# LED.net
KiCad netlist of a schematic drawn in Altium Designer
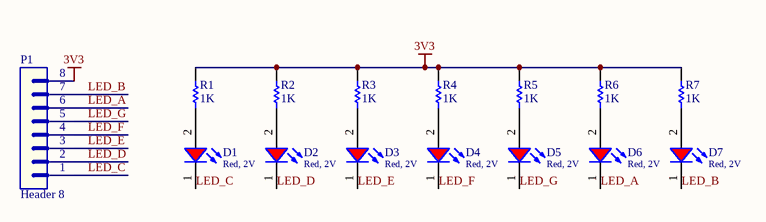
[diagram p0: LED.SchDoc]

(export (version "E")
  (design (tool "Eeschema 10.0.6"))
  (components
    (comp (ref "D1")
      (value "Red, 2V")
      (footprint "WL-SMCW_0805")
      (description "WL-SMCW SMT Mono-color Chip LED Waterclear, size 0805, Red, 2V, 140deg")
      (fields (field (name "PART NUMBER") "150080RS75000") (field (name "PUBLISHER") "Wurth Elektronik"))
      (libsource (lib "LED_GREEN") (part "150080RS75000"))
    )
    (comp (ref "D2")
      (value "Red, 2V")
      (footprint "WL-SMCW_0805")
      (description "WL-SMCW SMT Mono-color Chip LED Waterclear, size 0805, Red, 2V, 140deg")
      (fields (field (name "PART NUMBER") "150080RS75000") (field (name "PUBLISHER") "Wurth Elektronik"))
      (libsource (lib "LED_GREEN") (part "150080RS75000"))
    )
    (comp (ref "D3")
      (value "Red, 2V")
      (footprint "WL-SMCW_0805")
      (description "WL-SMCW SMT Mono-color Chip LED Waterclear, size 0805, Red, 2V, 140deg")
      (fields (field (name "PART NUMBER") "150080RS75000") (field (name "PUBLISHER") "Wurth Elektronik"))
      (libsource (lib "LED_GREEN") (part "150080RS75000"))
    )
    (comp (ref "D4")
      (value "Red, 2V")
      (footprint "WL-SMCW_0805")
      (description "WL-SMCW SMT Mono-color Chip LED Waterclear, size 0805, Red, 2V, 140deg")
      (fields (field (name "PART NUMBER") "150080RS75000") (field (name "PUBLISHER") "Wurth Elektronik"))
      (libsource (lib "LED_GREEN") (part "150080RS75000"))
    )
    (comp (ref "D5")
      (value "Red, 2V")
      (footprint "WL-SMCW_0805")
      (description "WL-SMCW SMT Mono-color Chip LED Waterclear, size 0805, Red, 2V, 140deg")
      (fields (field (name "PART NUMBER") "150080RS75000") (field (name "PUBLISHER") "Wurth Elektronik"))
      (libsource (lib "LED_GREEN") (part "150080RS75000"))
    )
    (comp (ref "D6")
      (value "Red, 2V")
      (footprint "WL-SMCW_0805")
      (description "WL-SMCW SMT Mono-color Chip LED Waterclear, size 0805, Red, 2V, 140deg")
      (fields (field (name "PART NUMBER") "150080RS75000") (field (name "PUBLISHER") "Wurth Elektronik"))
      (libsource (lib "LED_GREEN") (part "150080RS75000"))
    )
    (comp (ref "D7")
      (value "Red, 2V")
      (footprint "WL-SMCW_0805")
      (description "WL-SMCW SMT Mono-color Chip LED Waterclear, size 0805, Red, 2V, 140deg")
      (fields (field (name "PART NUMBER") "150080RS75000") (field (name "PUBLISHER") "Wurth Elektronik"))
      (libsource (lib "LED_GREEN") (part "150080RS75000"))
    )
    (comp (ref "P1")
      (value "Header 8")
      (footprint "JP8")
      (description "Header, 8-Pin")
      (fields (field (name "PUBLISHER") "Altium Limited"))
      (libsource (lib "Header-connector") (part "Header 8"))
    )
    (comp (ref "R1")
      (value "1K")
      (footprint "Resistor:RES-SM-0805")
      (description "RES 1K OHM 1% 1/4W 0805")
      (fields
        (field (name "MANUFACTURER") "Stackpole Electronics Inc")
        (field (name "MANUFACTURER PART NUMBER") "RNCP0805FTD1K00")
      )
      (libsource (lib "Resistor") (part "Res-1K-0805"))
    )
    (comp (ref "R2")
      (value "1K")
      (footprint "Resistor:RES-SM-0805")
      (description "RES 1K OHM 1% 1/4W 0805")
      (fields
        (field (name "MANUFACTURER") "Stackpole Electronics Inc")
        (field (name "MANUFACTURER PART NUMBER") "RNCP0805FTD1K00")
      )
      (libsource (lib "Resistor") (part "Res-1K-0805"))
    )
    (comp (ref "R3")
      (value "1K")
      (footprint "Resistor:RES-SM-0805")
      (description "RES 1K OHM 1% 1/4W 0805")
      (fields
        (field (name "MANUFACTURER") "Stackpole Electronics Inc")
        (field (name "MANUFACTURER PART NUMBER") "RNCP0805FTD1K00")
      )
      (libsource (lib "Resistor") (part "Res-1K-0805"))
    )
    (comp (ref "R4")
      (value "1K")
      (footprint "Resistor:RES-SM-0805")
      (description "RES 1K OHM 1% 1/4W 0805")
      (fields
        (field (name "MANUFACTURER") "Stackpole Electronics Inc")
        (field (name "MANUFACTURER PART NUMBER") "RNCP0805FTD1K00")
      )
      (libsource (lib "Resistor") (part "Res-1K-0805"))
    )
    (comp (ref "R5")
      (value "1K")
      (footprint "Resistor:RES-SM-0805")
      (description "RES 1K OHM 1% 1/4W 0805")
      (fields
        (field (name "MANUFACTURER") "Stackpole Electronics Inc")
        (field (name "MANUFACTURER PART NUMBER") "RNCP0805FTD1K00")
      )
      (libsource (lib "Resistor") (part "Res-1K-0805"))
    )
    (comp (ref "R6")
      (value "1K")
      (footprint "Resistor:RES-SM-0805")
      (description "RES 1K OHM 1% 1/4W 0805")
      (fields
        (field (name "MANUFACTURER") "Stackpole Electronics Inc")
        (field (name "MANUFACTURER PART NUMBER") "RNCP0805FTD1K00")
      )
      (libsource (lib "Resistor") (part "Res-1K-0805"))
    )
    (comp (ref "R7")
      (value "1K")
      (footprint "Resistor:RES-SM-0805")
      (description "RES 1K OHM 1% 1/4W 0805")
      (fields
        (field (name "MANUFACTURER") "Stackpole Electronics Inc")
        (field (name "MANUFACTURER PART NUMBER") "RNCP0805FTD1K00")
      )
      (libsource (lib "Resistor") (part "Res-1K-0805"))
    )
  )
  (nets
    (net (code "1") (name "/LED_A") (class "Default")
      (node (ref "D6") (pin "1") (pinfunction "K_1") (pintype "passive"))
      (node (ref "P1") (pin "6") (pinfunction "6_6") (pintype "passive"))
    )
    (net (code "2") (name "/LED_B") (class "Default")
      (node (ref "D7") (pin "1") (pinfunction "K_1") (pintype "passive"))
      (node (ref "P1") (pin "7") (pinfunction "7_7") (pintype "passive"))
    )
    (net (code "3") (name "/LED_C") (class "Default")
      (node (ref "D1") (pin "1") (pinfunction "K_1") (pintype "passive"))
      (node (ref "P1") (pin "1") (pinfunction "1_1") (pintype "passive"))
    )
    (net (code "4") (name "/LED_D") (class "Default")
      (node (ref "D2") (pin "1") (pinfunction "K_1") (pintype "passive"))
      (node (ref "P1") (pin "2") (pinfunction "2_2") (pintype "passive"))
    )
    (net (code "5") (name "/LED_E") (class "Default")
      (node (ref "D3") (pin "1") (pinfunction "K_1") (pintype "passive"))
      (node (ref "P1") (pin "3") (pinfunction "3_3") (pintype "passive"))
    )
    (net (code "6") (name "/LED_F") (class "Default")
      (node (ref "D4") (pin "1") (pinfunction "K_1") (pintype "passive"))
      (node (ref "P1") (pin "4") (pinfunction "4_4") (pintype "passive"))
    )
    (net (code "7") (name "/LED_G") (class "Default")
      (node (ref "D5") (pin "1") (pinfunction "K_1") (pintype "passive"))
      (node (ref "P1") (pin "5") (pinfunction "5_5") (pintype "passive"))
    )
    (net (code "8") (name "3V3") (class "Default")
      (node (ref "P1") (pin "8") (pinfunction "8_8") (pintype "passive"))
      (node (ref "R1") (pin "2") (pinfunction "2_2") (pintype "passive"))
      (node (ref "R2") (pin "2") (pinfunction "2_2") (pintype "passive"))
      (node (ref "R3") (pin "2") (pinfunction "2_2") (pintype "passive"))
      (node (ref "R4") (pin "2") (pinfunction "2_2") (pintype "passive"))
      (node (ref "R5") (pin "2") (pinfunction "2_2") (pintype "passive"))
      (node (ref "R6") (pin "2") (pinfunction "2_2") (pintype "passive"))
      (node (ref "R7") (pin "2") (pinfunction "2_2") (pintype "passive"))
    )
    (net (code "9") (name "Net-(D1-A)") (class "Default")
      (node (ref "D1") (pin "2") (pinfunction "A_2") (pintype "passive"))
      (node (ref "R1") (pin "1") (pinfunction "1_1") (pintype "passive"))
    )
    (net (code "10") (name "Net-(D2-A)") (class "Default")
      (node (ref "D2") (pin "2") (pinfunction "A_2") (pintype "passive"))
      (node (ref "R2") (pin "1") (pinfunction "1_1") (pintype "passive"))
    )
    (net (code "11") (name "Net-(D3-A)") (class "Default")
      (node (ref "D3") (pin "2") (pinfunction "A_2") (pintype "passive"))
      (node (ref "R3") (pin "1") (pinfunction "1_1") (pintype "passive"))
    )
    (net (code "12") (name "Net-(D4-A)") (class "Default")
      (node (ref "D4") (pin "2") (pinfunction "A_2") (pintype "passive"))
      (node (ref "R4") (pin "1") (pinfunction "1_1") (pintype "passive"))
    )
    (net (code "13") (name "Net-(D5-A)") (class "Default")
      (node (ref "D5") (pin "2") (pinfunction "A_2") (pintype "passive"))
      (node (ref "R5") (pin "1") (pinfunction "1_1") (pintype "passive"))
    )
    (net (code "14") (name "Net-(D6-A)") (class "Default")
      (node (ref "D6") (pin "2") (pinfunction "A_2") (pintype "passive"))
      (node (ref "R6") (pin "1") (pinfunction "1_1") (pintype "passive"))
    )
    (net (code "15") (name "Net-(D7-A)") (class "Default")
      (node (ref "D7") (pin "2") (pinfunction "A_2") (pintype "passive"))
      (node (ref "R7") (pin "1") (pinfunction "1_1") (pintype "passive"))
    )
  )
)
